# LEDStatusBoard.net
KiCad netlist of a schematic drawn in EAGLE
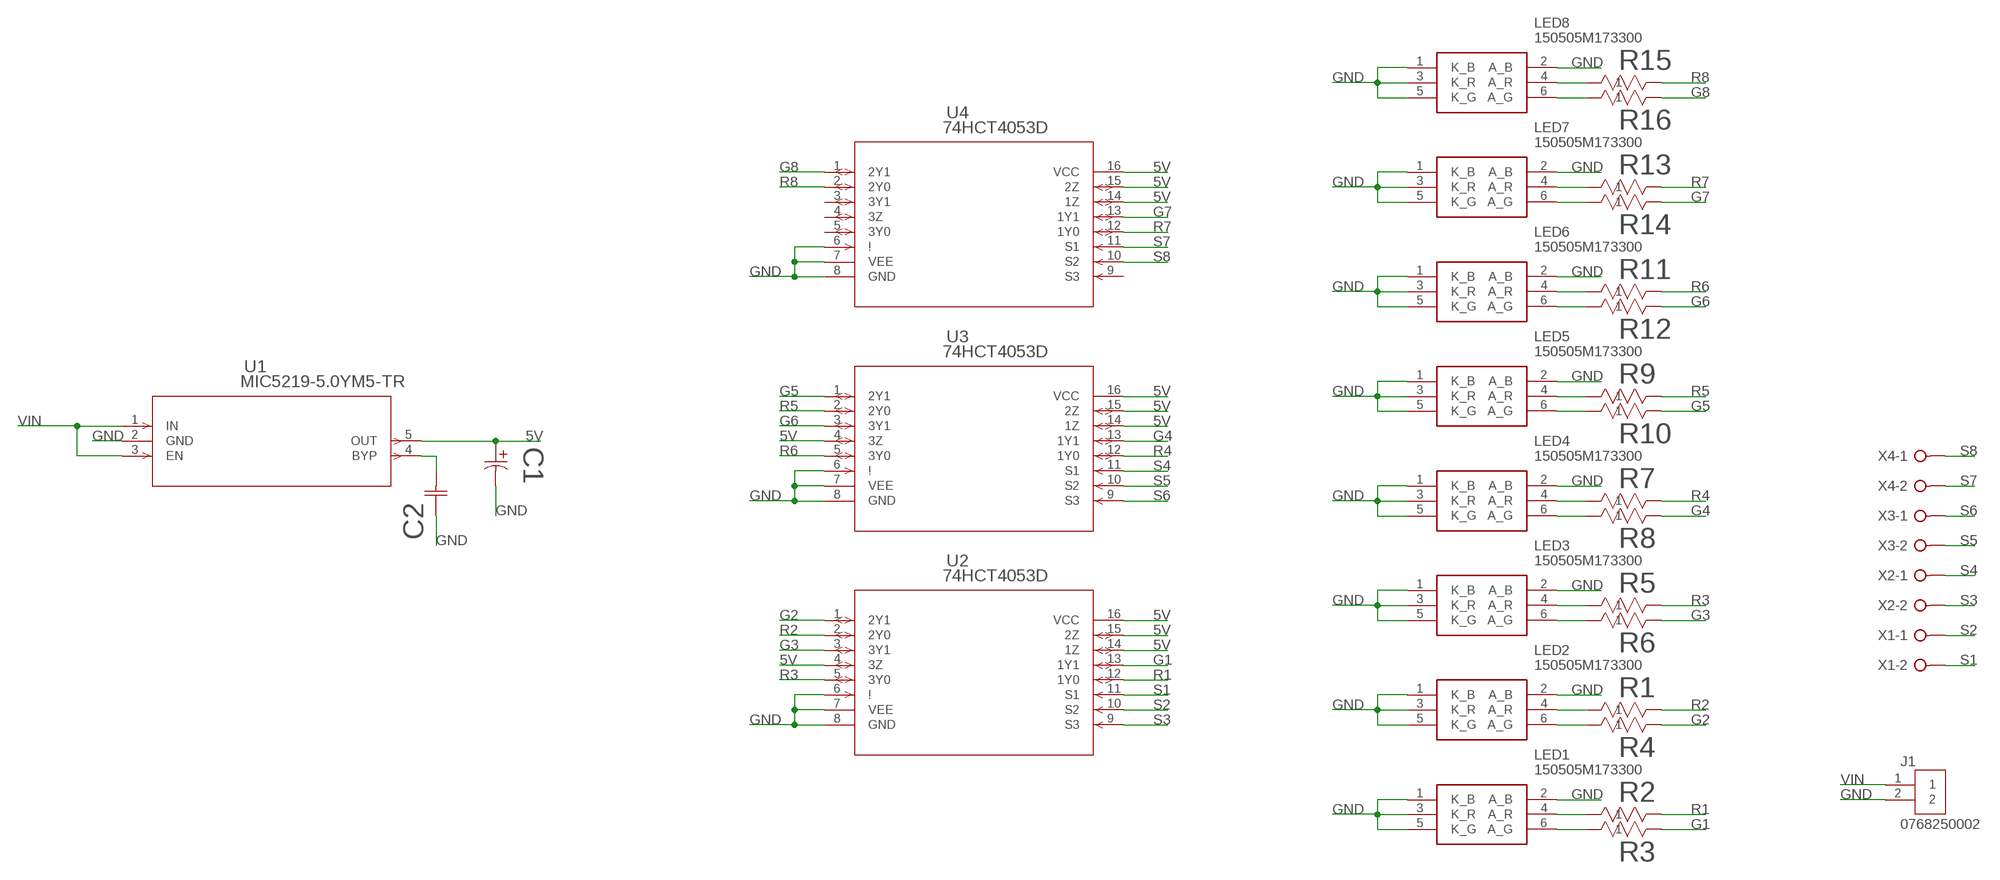
[diagram p0: schematic, sheet 1]

(export (version "E")
  (design (tool "Eeschema 10.0.6"))
  (components
    (comp (ref "C1")
      (value "UWX1H2R2MCL1GB")
      (footprint "eagle-import:PCAP_4X5.4-ELECT_NCA")
      (libsource (lib "eagle-import") (part "UWX1H2R2MCL1GB"))
    )
    (comp (ref "C2")
      (value "1206AA471JAT1A")
      (footprint "eagle-import:CAP_1206_AVX")
      (fields (field (name "COPYRIGHT") "Copyright (C) 2018 Accelerated Designs. All rights reserved"))
      (libsource (lib "eagle-import") (part "1206AA471JAT1A"))
    )
    (comp (ref "J1")
      (value "0768250002")
      (footprint "eagle-import:MOLEX_0768250002")
      (fields (field (name "MF") "Molex"))
      (libsource (lib "eagle-import") (part "0768250002"))
    )
    (comp (ref "LED1")
      (value "150505M173300")
      (footprint "eagle-import:150505M173300")
      (fields (field (name "MOUSER_PART_NUMBER") "710-150505M173300"))
      (libsource (lib "eagle-import") (part "150505M173300"))
    )
    (comp (ref "LED2")
      (value "150505M173300")
      (footprint "eagle-import:150505M173300")
      (fields (field (name "MOUSER_PART_NUMBER") "710-150505M173300"))
      (libsource (lib "eagle-import") (part "150505M173300"))
    )
    (comp (ref "LED3")
      (value "150505M173300")
      (footprint "eagle-import:150505M173300")
      (fields (field (name "MOUSER_PART_NUMBER") "710-150505M173300"))
      (libsource (lib "eagle-import") (part "150505M173300"))
    )
    (comp (ref "LED4")
      (value "150505M173300")
      (footprint "eagle-import:150505M173300")
      (fields (field (name "MOUSER_PART_NUMBER") "710-150505M173300"))
      (libsource (lib "eagle-import") (part "150505M173300"))
    )
    (comp (ref "LED5")
      (value "150505M173300")
      (footprint "eagle-import:150505M173300")
      (fields (field (name "MOUSER_PART_NUMBER") "710-150505M173300"))
      (libsource (lib "eagle-import") (part "150505M173300"))
    )
    (comp (ref "LED6")
      (value "150505M173300")
      (footprint "eagle-import:150505M173300")
      (fields (field (name "MOUSER_PART_NUMBER") "710-150505M173300"))
      (libsource (lib "eagle-import") (part "150505M173300"))
    )
    (comp (ref "LED7")
      (value "150505M173300")
      (footprint "eagle-import:150505M173300")
      (fields (field (name "MOUSER_PART_NUMBER") "710-150505M173300"))
      (libsource (lib "eagle-import") (part "150505M173300"))
    )
    (comp (ref "LED8")
      (value "150505M173300")
      (footprint "eagle-import:150505M173300")
      (fields (field (name "MOUSER_PART_NUMBER") "710-150505M173300"))
      (libsource (lib "eagle-import") (part "150505M173300"))
    )
    (comp (ref "R1")
      (value "RMCF1206JT130R")
      (footprint "eagle-import:RES_RMCF1206_STP")
      (fields (field (name "COPYRIGHT") "Copyright (C) 2018 Accelerated Designs. All rights reserved"))
      (libsource (lib "eagle-import") (part "RMCF1206JT130R"))
    )
    (comp (ref "R2")
      (value "RMCF1206JT130R")
      (footprint "eagle-import:RES_RMCF1206_STP")
      (fields (field (name "COPYRIGHT") "Copyright (C) 2018 Accelerated Designs. All rights reserved"))
      (libsource (lib "eagle-import") (part "RMCF1206JT130R"))
    )
    (comp (ref "R3")
      (value "RMCF1206JT130R")
      (footprint "eagle-import:RES_RMCF1206_STP")
      (fields (field (name "COPYRIGHT") "Copyright (C) 2018 Accelerated Designs. All rights reserved"))
      (libsource (lib "eagle-import") (part "RMCF1206JT130R"))
    )
    (comp (ref "R4")
      (value "RMCF1206JT130R")
      (footprint "eagle-import:RES_RMCF1206_STP")
      (fields (field (name "COPYRIGHT") "Copyright (C) 2018 Accelerated Designs. All rights reserved"))
      (libsource (lib "eagle-import") (part "RMCF1206JT130R"))
    )
    (comp (ref "R5")
      (value "RMCF1206JT130R")
      (footprint "eagle-import:RES_RMCF1206_STP")
      (fields (field (name "COPYRIGHT") "Copyright (C) 2018 Accelerated Designs. All rights reserved"))
      (libsource (lib "eagle-import") (part "RMCF1206JT130R"))
    )
    (comp (ref "R6")
      (value "RMCF1206JT130R")
      (footprint "eagle-import:RES_RMCF1206_STP")
      (fields (field (name "COPYRIGHT") "Copyright (C) 2018 Accelerated Designs. All rights reserved"))
      (libsource (lib "eagle-import") (part "RMCF1206JT130R"))
    )
    (comp (ref "R7")
      (value "RMCF1206JT130R")
      (footprint "eagle-import:RES_RMCF1206_STP")
      (fields (field (name "COPYRIGHT") "Copyright (C) 2018 Accelerated Designs. All rights reserved"))
      (libsource (lib "eagle-import") (part "RMCF1206JT130R"))
    )
    (comp (ref "R8")
      (value "RMCF1206JT130R")
      (footprint "eagle-import:RES_RMCF1206_STP")
      (fields (field (name "COPYRIGHT") "Copyright (C) 2018 Accelerated Designs. All rights reserved"))
      (libsource (lib "eagle-import") (part "RMCF1206JT130R"))
    )
    (comp (ref "R9")
      (value "RMCF1206JT130R")
      (footprint "eagle-import:RES_RMCF1206_STP")
      (fields (field (name "COPYRIGHT") "Copyright (C) 2018 Accelerated Designs. All rights reserved"))
      (libsource (lib "eagle-import") (part "RMCF1206JT130R"))
    )
    (comp (ref "R10")
      (value "RMCF1206JT130R")
      (footprint "eagle-import:RES_RMCF1206_STP")
      (fields (field (name "COPYRIGHT") "Copyright (C) 2018 Accelerated Designs. All rights reserved"))
      (libsource (lib "eagle-import") (part "RMCF1206JT130R"))
    )
    (comp (ref "R11")
      (value "RMCF1206JT130R")
      (footprint "eagle-import:RES_RMCF1206_STP")
      (fields (field (name "COPYRIGHT") "Copyright (C) 2018 Accelerated Designs. All rights reserved"))
      (libsource (lib "eagle-import") (part "RMCF1206JT130R"))
    )
    (comp (ref "R12")
      (value "RMCF1206JT130R")
      (footprint "eagle-import:RES_RMCF1206_STP")
      (fields (field (name "COPYRIGHT") "Copyright (C) 2018 Accelerated Designs. All rights reserved"))
      (libsource (lib "eagle-import") (part "RMCF1206JT130R"))
    )
    (comp (ref "R13")
      (value "RMCF1206JT130R")
      (footprint "eagle-import:RES_RMCF1206_STP")
      (fields (field (name "COPYRIGHT") "Copyright (C) 2018 Accelerated Designs. All rights reserved"))
      (libsource (lib "eagle-import") (part "RMCF1206JT130R"))
    )
    (comp (ref "R14")
      (value "RMCF1206JT130R")
      (footprint "eagle-import:RES_RMCF1206_STP")
      (fields (field (name "COPYRIGHT") "Copyright (C) 2018 Accelerated Designs. All rights reserved"))
      (libsource (lib "eagle-import") (part "RMCF1206JT130R"))
    )
    (comp (ref "R15")
      (value "RMCF1206JT130R")
      (footprint "eagle-import:RES_RMCF1206_STP")
      (fields (field (name "COPYRIGHT") "Copyright (C) 2018 Accelerated Designs. All rights reserved"))
      (libsource (lib "eagle-import") (part "RMCF1206JT130R"))
    )
    (comp (ref "R16")
      (value "RMCF1206JT130R")
      (footprint "eagle-import:RES_RMCF1206_STP")
      (fields (field (name "COPYRIGHT") "Copyright (C) 2018 Accelerated Designs. All rights reserved"))
      (libsource (lib "eagle-import") (part "RMCF1206JT130R"))
    )
    (comp (ref "U1")
      (value "MIC5219-5.0YM5-TR")
      (footprint "eagle-import:SOT-23-5_M5_MCH")
      (fields (field (name "COPYRIGHT") "Copyright (C) 2018 Accelerated Designs. All rights reserved"))
      (libsource (lib "eagle-import") (part "MIC5219-5.0YM5-TR"))
    )
    (comp (ref "U2")
      (value "74HCT4053D")
      (footprint "eagle-import:SOT109-1_NXP")
      (libsource (lib "eagle-import") (part "74HCT4053D"))
    )
    (comp (ref "U3")
      (value "74HCT4053D")
      (footprint "eagle-import:SOT109-1_NXP")
      (libsource (lib "eagle-import") (part "74HCT4053D"))
    )
    (comp (ref "U4")
      (value "74HCT4053D")
      (footprint "eagle-import:SOT109-1_NXP")
      (libsource (lib "eagle-import") (part "74HCT4053D"))
    )
    (comp (ref "X1")
      (value "W237-02P")
      (footprint "eagle-import:W237-132")
      (libsource (lib "eagle-import") (part "W237-02P"))
    )
    (comp (ref "X2")
      (value "W237-02P")
      (footprint "eagle-import:W237-132")
      (libsource (lib "eagle-import") (part "W237-02P"))
    )
    (comp (ref "X3")
      (value "W237-02P")
      (footprint "eagle-import:W237-132")
      (libsource (lib "eagle-import") (part "W237-02P"))
    )
    (comp (ref "X4")
      (value "W237-02P")
      (footprint "eagle-import:W237-132")
      (libsource (lib "eagle-import") (part "W237-02P"))
    )
  )
  (nets
    (net (code "1") (name "/5V") (class "Default")
      (node (ref "C1") (pin "1") (pinfunction "1_1") (pintype "passive"))
      (node (ref "U1") (pin "5") (pinfunction "OUT_5") (pintype "output"))
      (node (ref "U2") (pin "14") (pinfunction "1Z_14") (pintype "bidirectional"))
      (node (ref "U2") (pin "15") (pinfunction "2Z_15") (pintype "bidirectional"))
      (node (ref "U2") (pin "16") (pinfunction "VCC_16") (pintype "power_in"))
      (node (ref "U2") (pin "4") (pinfunction "3Z_4") (pintype "bidirectional"))
      (node (ref "U3") (pin "14") (pinfunction "1Z_14") (pintype "bidirectional"))
      (node (ref "U3") (pin "15") (pinfunction "2Z_15") (pintype "bidirectional"))
      (node (ref "U3") (pin "16") (pinfunction "VCC_16") (pintype "power_in"))
      (node (ref "U3") (pin "4") (pinfunction "3Z_4") (pintype "bidirectional"))
      (node (ref "U4") (pin "14") (pinfunction "1Z_14") (pintype "bidirectional"))
      (node (ref "U4") (pin "15") (pinfunction "2Z_15") (pintype "bidirectional"))
      (node (ref "U4") (pin "16") (pinfunction "VCC_16") (pintype "power_in"))
    )
    (net (code "2") (name "/G1") (class "Default")
      (node (ref "R3") (pin "2") (pinfunction "2_2") (pintype "passive"))
      (node (ref "U2") (pin "13") (pinfunction "1Y1_13") (pintype "bidirectional"))
    )
    (net (code "3") (name "/G2") (class "Default")
      (node (ref "R4") (pin "2") (pinfunction "2_2") (pintype "passive"))
      (node (ref "U2") (pin "1") (pinfunction "2Y1_1") (pintype "bidirectional"))
    )
    (net (code "4") (name "/G3") (class "Default")
      (node (ref "R6") (pin "2") (pinfunction "2_2") (pintype "passive"))
      (node (ref "U2") (pin "3") (pinfunction "3Y1_3") (pintype "bidirectional"))
    )
    (net (code "5") (name "/G4") (class "Default")
      (node (ref "R8") (pin "2") (pinfunction "2_2") (pintype "passive"))
      (node (ref "U3") (pin "13") (pinfunction "1Y1_13") (pintype "bidirectional"))
    )
    (net (code "6") (name "/G5") (class "Default")
      (node (ref "R10") (pin "2") (pinfunction "2_2") (pintype "passive"))
      (node (ref "U3") (pin "1") (pinfunction "2Y1_1") (pintype "bidirectional"))
    )
    (net (code "7") (name "/G6") (class "Default")
      (node (ref "R12") (pin "2") (pinfunction "2_2") (pintype "passive"))
      (node (ref "U3") (pin "3") (pinfunction "3Y1_3") (pintype "bidirectional"))
    )
    (net (code "8") (name "/G7") (class "Default")
      (node (ref "R14") (pin "2") (pinfunction "2_2") (pintype "passive"))
      (node (ref "U4") (pin "13") (pinfunction "1Y1_13") (pintype "bidirectional"))
    )
    (net (code "9") (name "/G8") (class "Default")
      (node (ref "R16") (pin "2") (pinfunction "2_2") (pintype "passive"))
      (node (ref "U4") (pin "1") (pinfunction "2Y1_1") (pintype "bidirectional"))
    )
    (net (code "10") (name "/GND") (class "Default")
      (node (ref "C1") (pin "2") (pinfunction "2_2") (pintype "passive"))
      (node (ref "C2") (pin "1") (pinfunction "1_1") (pintype "passive"))
      (node (ref "J1") (pin "2") (pinfunction "2_2") (pintype "passive"))
      (node (ref "LED1") (pin "1") (pinfunction "K_B_1") (pintype "bidirectional"))
      (node (ref "LED1") (pin "2") (pinfunction "A_B_2") (pintype "bidirectional"))
      (node (ref "LED1") (pin "3") (pinfunction "K_R_3") (pintype "bidirectional"))
      (node (ref "LED1") (pin "5") (pinfunction "K_G_5") (pintype "bidirectional"))
      (node (ref "LED2") (pin "1") (pinfunction "K_B_1") (pintype "bidirectional"))
      (node (ref "LED2") (pin "2") (pinfunction "A_B_2") (pintype "bidirectional"))
      (node (ref "LED2") (pin "3") (pinfunction "K_R_3") (pintype "bidirectional"))
      (node (ref "LED2") (pin "5") (pinfunction "K_G_5") (pintype "bidirectional"))
      (node (ref "LED3") (pin "1") (pinfunction "K_B_1") (pintype "bidirectional"))
      (node (ref "LED3") (pin "2") (pinfunction "A_B_2") (pintype "bidirectional"))
      (node (ref "LED3") (pin "3") (pinfunction "K_R_3") (pintype "bidirectional"))
      (node (ref "LED3") (pin "5") (pinfunction "K_G_5") (pintype "bidirectional"))
      (node (ref "LED4") (pin "1") (pinfunction "K_B_1") (pintype "bidirectional"))
      (node (ref "LED4") (pin "2") (pinfunction "A_B_2") (pintype "bidirectional"))
      (node (ref "LED4") (pin "3") (pinfunction "K_R_3") (pintype "bidirectional"))
      (node (ref "LED4") (pin "5") (pinfunction "K_G_5") (pintype "bidirectional"))
      (node (ref "LED5") (pin "1") (pinfunction "K_B_1") (pintype "bidirectional"))
      (node (ref "LED5") (pin "2") (pinfunction "A_B_2") (pintype "bidirectional"))
      (node (ref "LED5") (pin "3") (pinfunction "K_R_3") (pintype "bidirectional"))
      (node (ref "LED5") (pin "5") (pinfunction "K_G_5") (pintype "bidirectional"))
      (node (ref "LED6") (pin "1") (pinfunction "K_B_1") (pintype "bidirectional"))
      (node (ref "LED6") (pin "2") (pinfunction "A_B_2") (pintype "bidirectional"))
      (node (ref "LED6") (pin "3") (pinfunction "K_R_3") (pintype "bidirectional"))
      (node (ref "LED6") (pin "5") (pinfunction "K_G_5") (pintype "bidirectional"))
      (node (ref "LED7") (pin "1") (pinfunction "K_B_1") (pintype "bidirectional"))
      (node (ref "LED7") (pin "2") (pinfunction "A_B_2") (pintype "bidirectional"))
      (node (ref "LED7") (pin "3") (pinfunction "K_R_3") (pintype "bidirectional"))
      (node (ref "LED7") (pin "5") (pinfunction "K_G_5") (pintype "bidirectional"))
      (node (ref "LED8") (pin "1") (pinfunction "K_B_1") (pintype "bidirectional"))
      (node (ref "LED8") (pin "2") (pinfunction "A_B_2") (pintype "bidirectional"))
      (node (ref "LED8") (pin "3") (pinfunction "K_R_3") (pintype "bidirectional"))
      (node (ref "LED8") (pin "5") (pinfunction "K_G_5") (pintype "bidirectional"))
      (node (ref "U1") (pin "2") (pinfunction "GND_2") (pintype "power_in"))
      (node (ref "U2") (pin "6") (pinfunction "~_6") (pintype "input"))
      (node (ref "U2") (pin "7") (pinfunction "VEE_7") (pintype "power_in"))
      (node (ref "U2") (pin "8") (pinfunction "GND_8") (pintype "power_in"))
      (node (ref "U3") (pin "6") (pinfunction "~_6") (pintype "input"))
      (node (ref "U3") (pin "7") (pinfunction "VEE_7") (pintype "power_in"))
      (node (ref "U3") (pin "8") (pinfunction "GND_8") (pintype "power_in"))
      (node (ref "U4") (pin "6") (pinfunction "~_6") (pintype "input"))
      (node (ref "U4") (pin "7") (pinfunction "VEE_7") (pintype "power_in"))
      (node (ref "U4") (pin "8") (pinfunction "GND_8") (pintype "power_in"))
    )
    (net (code "11") (name "/R1") (class "Default")
      (node (ref "R2") (pin "2") (pinfunction "2_2") (pintype "passive"))
      (node (ref "U2") (pin "12") (pinfunction "1Y0_12") (pintype "bidirectional"))
    )
    (net (code "12") (name "/R2") (class "Default")
      (node (ref "R1") (pin "2") (pinfunction "2_2") (pintype "passive"))
      (node (ref "U2") (pin "2") (pinfunction "2Y0_2") (pintype "bidirectional"))
    )
    (net (code "13") (name "/R3") (class "Default")
      (node (ref "R5") (pin "2") (pinfunction "2_2") (pintype "passive"))
      (node (ref "U2") (pin "5") (pinfunction "3Y0_5") (pintype "bidirectional"))
    )
    (net (code "14") (name "/R4") (class "Default")
      (node (ref "R7") (pin "2") (pinfunction "2_2") (pintype "passive"))
      (node (ref "U3") (pin "12") (pinfunction "1Y0_12") (pintype "bidirectional"))
    )
    (net (code "15") (name "/R5") (class "Default")
      (node (ref "R9") (pin "2") (pinfunction "2_2") (pintype "passive"))
      (node (ref "U3") (pin "2") (pinfunction "2Y0_2") (pintype "bidirectional"))
    )
    (net (code "16") (name "/R6") (class "Default")
      (node (ref "R11") (pin "2") (pinfunction "2_2") (pintype "passive"))
      (node (ref "U3") (pin "5") (pinfunction "3Y0_5") (pintype "bidirectional"))
    )
    (net (code "17") (name "/R7") (class "Default")
      (node (ref "R13") (pin "2") (pinfunction "2_2") (pintype "passive"))
      (node (ref "U4") (pin "12") (pinfunction "1Y0_12") (pintype "bidirectional"))
    )
    (net (code "18") (name "/R8") (class "Default")
      (node (ref "R15") (pin "2") (pinfunction "2_2") (pintype "passive"))
      (node (ref "U4") (pin "2") (pinfunction "2Y0_2") (pintype "bidirectional"))
    )
    (net (code "19") (name "/S1") (class "Default")
      (node (ref "U2") (pin "11") (pinfunction "S1_11") (pintype "input"))
      (node (ref "X1") (pin "2") (pinfunction "KL_2") (pintype "passive"))
    )
    (net (code "20") (name "/S2") (class "Default")
      (node (ref "U2") (pin "10") (pinfunction "S2_10") (pintype "input"))
      (node (ref "X1") (pin "1") (pinfunction "KL_1") (pintype "passive"))
    )
    (net (code "21") (name "/S3") (class "Default")
      (node (ref "U2") (pin "9") (pinfunction "S3_9") (pintype "input"))
      (node (ref "X2") (pin "2") (pinfunction "KL_2") (pintype "passive"))
    )
    (net (code "22") (name "/S4") (class "Default")
      (node (ref "U3") (pin "11") (pinfunction "S1_11") (pintype "input"))
      (node (ref "X2") (pin "1") (pinfunction "KL_1") (pintype "passive"))
    )
    (net (code "23") (name "/S5") (class "Default")
      (node (ref "U3") (pin "10") (pinfunction "S2_10") (pintype "input"))
      (node (ref "X3") (pin "2") (pinfunction "KL_2") (pintype "passive"))
    )
    (net (code "24") (name "/S6") (class "Default")
      (node (ref "U3") (pin "9") (pinfunction "S3_9") (pintype "input"))
      (node (ref "X3") (pin "1") (pinfunction "KL_1") (pintype "passive"))
    )
    (net (code "25") (name "/S7") (class "Default")
      (node (ref "U4") (pin "11") (pinfunction "S1_11") (pintype "input"))
      (node (ref "X4") (pin "2") (pinfunction "KL_2") (pintype "passive"))
    )
    (net (code "26") (name "/S8") (class "Default")
      (node (ref "U4") (pin "10") (pinfunction "S2_10") (pintype "input"))
      (node (ref "X4") (pin "1") (pinfunction "KL_1") (pintype "passive"))
    )
    (net (code "27") (name "/VIN") (class "Default")
      (node (ref "J1") (pin "1") (pinfunction "1_1") (pintype "passive"))
      (node (ref "U1") (pin "1") (pinfunction "IN_1") (pintype "input"))
      (node (ref "U1") (pin "3") (pinfunction "EN_3") (pintype "input"))
    )
    (net (code "28") (name "Net-(LED1-A_G)") (class "Default")
      (node (ref "LED1") (pin "6") (pinfunction "A_G_6") (pintype "bidirectional"))
      (node (ref "R3") (pin "1") (pinfunction "1_1") (pintype "passive"))
    )
    (net (code "29") (name "Net-(LED1-A_R)") (class "Default")
      (node (ref "LED1") (pin "4") (pinfunction "A_R_4") (pintype "bidirectional"))
      (node (ref "R2") (pin "1") (pinfunction "1_1") (pintype "passive"))
    )
    (net (code "30") (name "Net-(LED2-A_G)") (class "Default")
      (node (ref "LED2") (pin "6") (pinfunction "A_G_6") (pintype "bidirectional"))
      (node (ref "R4") (pin "1") (pinfunction "1_1") (pintype "passive"))
    )
    (net (code "31") (name "Net-(LED2-A_R)") (class "Default")
      (node (ref "LED2") (pin "4") (pinfunction "A_R_4") (pintype "bidirectional"))
      (node (ref "R1") (pin "1") (pinfunction "1_1") (pintype "passive"))
    )
    (net (code "32") (name "Net-(LED3-A_G)") (class "Default")
      (node (ref "LED3") (pin "6") (pinfunction "A_G_6") (pintype "bidirectional"))
      (node (ref "R6") (pin "1") (pinfunction "1_1") (pintype "passive"))
    )
    (net (code "33") (name "Net-(LED3-A_R)") (class "Default")
      (node (ref "LED3") (pin "4") (pinfunction "A_R_4") (pintype "bidirectional"))
      (node (ref "R5") (pin "1") (pinfunction "1_1") (pintype "passive"))
    )
    (net (code "34") (name "Net-(LED4-A_G)") (class "Default")
      (node (ref "LED4") (pin "6") (pinfunction "A_G_6") (pintype "bidirectional"))
      (node (ref "R8") (pin "1") (pinfunction "1_1") (pintype "passive"))
    )
    (net (code "35") (name "Net-(LED4-A_R)") (class "Default")
      (node (ref "LED4") (pin "4") (pinfunction "A_R_4") (pintype "bidirectional"))
      (node (ref "R7") (pin "1") (pinfunction "1_1") (pintype "passive"))
    )
    (net (code "36") (name "Net-(LED5-A_G)") (class "Default")
      (node (ref "LED5") (pin "6") (pinfunction "A_G_6") (pintype "bidirectional"))
      (node (ref "R10") (pin "1") (pinfunction "1_1") (pintype "passive"))
    )
    (net (code "37") (name "Net-(LED5-A_R)") (class "Default")
      (node (ref "LED5") (pin "4") (pinfunction "A_R_4") (pintype "bidirectional"))
      (node (ref "R9") (pin "1") (pinfunction "1_1") (pintype "passive"))
    )
    (net (code "38") (name "Net-(LED6-A_G)") (class "Default")
      (node (ref "LED6") (pin "6") (pinfunction "A_G_6") (pintype "bidirectional"))
      (node (ref "R12") (pin "1") (pinfunction "1_1") (pintype "passive"))
    )
    (net (code "39") (name "Net-(LED6-A_R)") (class "Default")
      (node (ref "LED6") (pin "4") (pinfunction "A_R_4") (pintype "bidirectional"))
      (node (ref "R11") (pin "1") (pinfunction "1_1") (pintype "passive"))
    )
    (net (code "40") (name "Net-(LED7-A_G)") (class "Default")
      (node (ref "LED7") (pin "6") (pinfunction "A_G_6") (pintype "bidirectional"))
      (node (ref "R14") (pin "1") (pinfunction "1_1") (pintype "passive"))
    )
    (net (code "41") (name "Net-(LED7-A_R)") (class "Default")
      (node (ref "LED7") (pin "4") (pinfunction "A_R_4") (pintype "bidirectional"))
      (node (ref "R13") (pin "1") (pinfunction "1_1") (pintype "passive"))
    )
    (net (code "42") (name "Net-(LED8-A_G)") (class "Default")
      (node (ref "LED8") (pin "6") (pinfunction "A_G_6") (pintype "bidirectional"))
      (node (ref "R16") (pin "1") (pinfunction "1_1") (pintype "passive"))
    )
    (net (code "43") (name "Net-(LED8-A_R)") (class "Default")
      (node (ref "LED8") (pin "4") (pinfunction "A_R_4") (pintype "bidirectional"))
      (node (ref "R15") (pin "1") (pinfunction "1_1") (pintype "passive"))
    )
    (net (code "44") (name "Net-(U1-BYP)") (class "Default")
      (node (ref "C2") (pin "2") (pinfunction "2_2") (pintype "passive"))
      (node (ref "U1") (pin "4") (pinfunction "BYP_4") (pintype "output"))
    )
    (net (code "45") (name "unconnected-(U4-3Y0-Pad5)") (class "Default")
      (node (ref "U4") (pin "5") (pinfunction "3Y0_5") (pintype "bidirectional"))
    )
    (net (code "46") (name "unconnected-(U4-3Y1-Pad3)") (class "Default")
      (node (ref "U4") (pin "3") (pinfunction "3Y1_3") (pintype "bidirectional"))
    )
    (net (code "47") (name "unconnected-(U4-3Z-Pad4)") (class "Default")
      (node (ref "U4") (pin "4") (pinfunction "3Z_4") (pintype "bidirectional"))
    )
    (net (code "48") (name "unconnected-(U4-S3-Pad9)") (class "Default")
      (node (ref "U4") (pin "9") (pinfunction "S3_9") (pintype "input"))
    )
  )
)
